# indoor_nearhandle_module.net
KiCad netlist of a schematic drawn in EAGLE
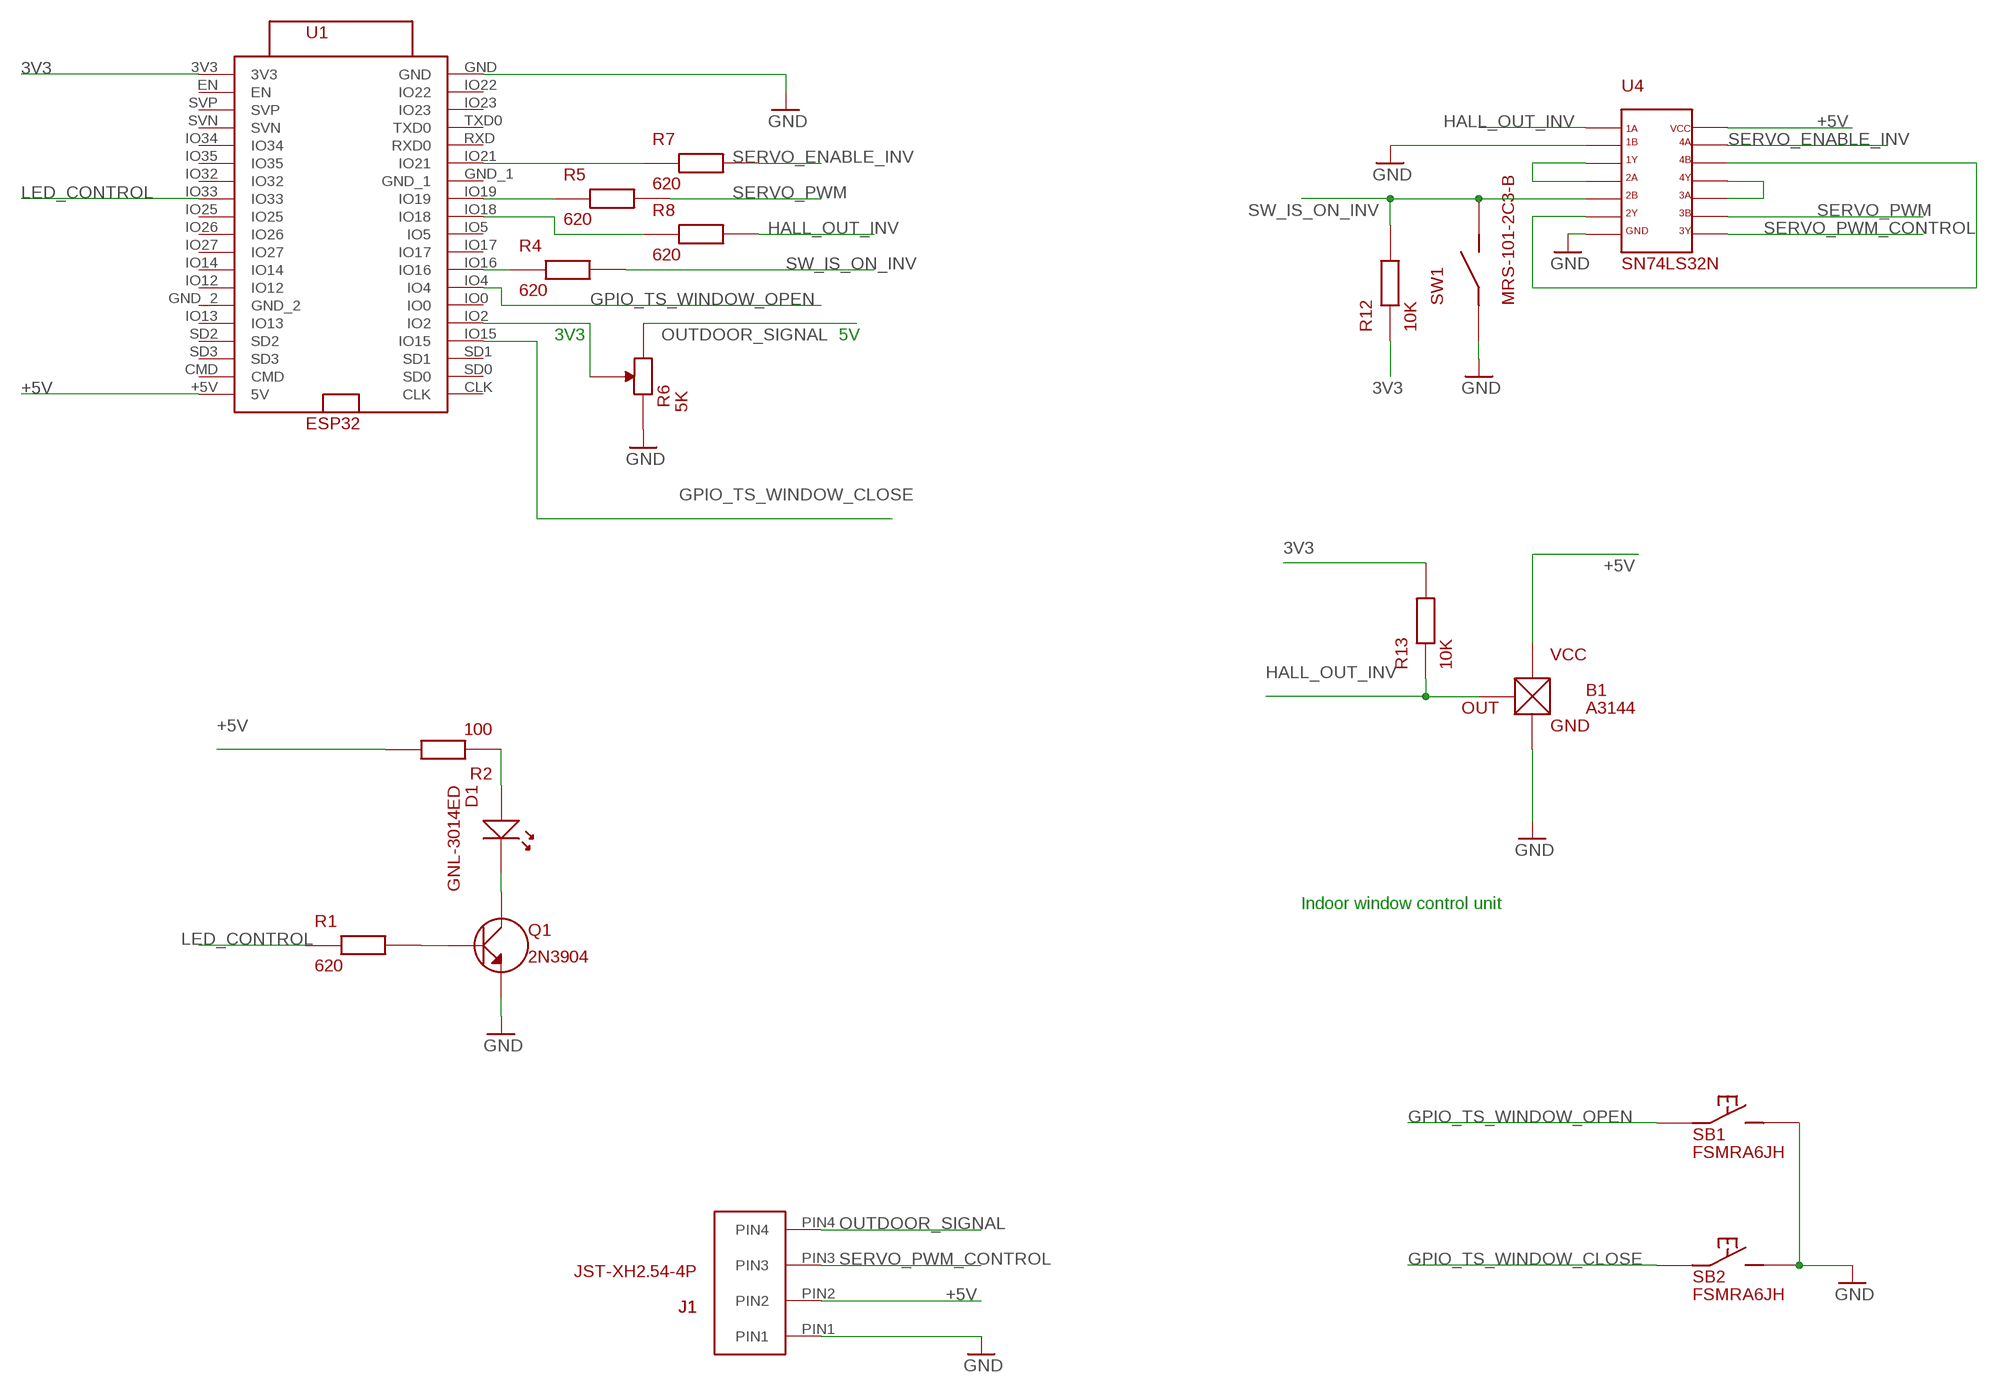
[diagram p0: schematic, sheet 1]

(export (version "E")
  (design (tool "Eeschema 10.0.6"))
  (components
    (comp (ref "B1")
      (value "A3144")
      (footprint "eagle-import:HALL_SENSOR")
      (libsource (lib "eagle-import") (part "HALL_SENSOR"))
    )
    (comp (ref "D1")
      (value "GNL-3014ED")
      (footprint "eagle-import:LD")
      (libsource (lib "eagle-import") (part "LD"))
    )
    (comp (ref "J1")
      (value "JST-XH2.54-4P")
      (footprint "eagle-import:JST-XH254-4P")
      (libsource (lib "eagle-import") (part "JST-XH254-4P"))
    )
    (comp (ref "Q1")
      (value "2N3904")
      (footprint "eagle-import:TRANSISTOR")
      (libsource (lib "eagle-import") (part "TRANSISTOR_NPN"))
    )
    (comp (ref "R1") (value "620") (footprint "eagle-import:R") (libsource (lib "eagle-import") (part "R")))
    (comp (ref "R2") (value "100") (footprint "eagle-import:R") (libsource (lib "eagle-import") (part "R")))
    (comp (ref "R4") (value "620") (footprint "eagle-import:R") (libsource (lib "eagle-import") (part "R")))
    (comp (ref "R5") (value "620") (footprint "eagle-import:R") (libsource (lib "eagle-import") (part "R")))
    (comp (ref "R6")
      (value "5K")
      (footprint "eagle-import:RD-3362H")
      (libsource (lib "eagle-import") (part "RD"))
    )
    (comp (ref "R7") (value "620") (footprint "eagle-import:R") (libsource (lib "eagle-import") (part "R")))
    (comp (ref "R8") (value "620") (footprint "eagle-import:R") (libsource (lib "eagle-import") (part "R")))
    (comp (ref "R12") (value "10K") (footprint "eagle-import:R") (libsource (lib "eagle-import") (part "R")))
    (comp (ref "R13") (value "10K") (footprint "eagle-import:R") (libsource (lib "eagle-import") (part "R")))
    (comp (ref "SB1")
      (value "FSMRA6JH")
      (footprint "eagle-import:SB-NO-SPST-ANGLE")
      (libsource (lib "eagle-import") (part "SB-NO"))
    )
    (comp (ref "SB2")
      (value "FSMRA6JH")
      (footprint "eagle-import:SB-NO-SPST-ANGLE")
      (libsource (lib "eagle-import") (part "SB-NO"))
    )
    (comp (ref "SW1")
      (value "MRS-101-2C3-B")
      (footprint "eagle-import:SWITCH")
      (libsource (lib "eagle-import") (part "SWITCH"))
    )
    (comp (ref "U1")
      (value "ESP32")
      (footprint "eagle-import:ESP32")
      (libsource (lib "eagle-import") (part "ESP32"))
    )
    (comp (ref "U4")
      (value "SN74LS32N")
      (footprint "eagle-import:DIP14")
      (libsource (lib "eagle-import") (part "SN74LS32N"))
    )
  )
  (nets
    (net (code "1") (name "/+5V") (class "Default")
      (node (ref "B1") (pin "VCC") (pinfunction "VCC_VCC") (pintype "power_in"))
      (node (ref "J1") (pin "PIN2") (pinfunction "PIN2_PIN2") (pintype "bidirectional"))
      (node (ref "R2") (pin "P$2") (pinfunction "P$2_P$2") (pintype "bidirectional"))
      (node (ref "U1") (pin "+5V") (pinfunction "5V_+5V") (pintype "power_in"))
      (node (ref "U4") (pin "PIN_14") (pinfunction "VCC_PIN_14") (pintype "power_in"))
    )
    (net (code "2") (name "/3V3") (class "Default")
      (node (ref "R12") (pin "P$1") (pinfunction "P$1_P$1") (pintype "bidirectional"))
      (node (ref "R13") (pin "P$2") (pinfunction "P$2_P$2") (pintype "bidirectional"))
      (node (ref "U1") (pin "3V3") (pinfunction "3V3_3V3") (pintype "power_in"))
    )
    (net (code "3") (name "/GPIO_TS_WINDOW_CLOSE") (class "Default")
      (node (ref "SB2") (pin "A") (pinfunction "P$1_A") (pintype "bidirectional"))
      (node (ref "U1") (pin "IO15") (pinfunction "IO15_IO15") (pintype "bidirectional"))
    )
    (net (code "4") (name "/GPIO_TS_WINDOW_OPEN") (class "Default")
      (node (ref "SB1") (pin "A") (pinfunction "P$1_A") (pintype "bidirectional"))
      (node (ref "U1") (pin "IO4") (pinfunction "IO4_IO4") (pintype "bidirectional"))
    )
    (net (code "5") (name "/HALL_OUT_INV") (class "Default")
      (node (ref "B1") (pin "OUT") (pinfunction "OUT_OUT") (pintype "bidirectional"))
      (node (ref "R13") (pin "P$1") (pinfunction "P$1_P$1") (pintype "bidirectional"))
      (node (ref "R8") (pin "P$2") (pinfunction "P$2_P$2") (pintype "bidirectional"))
      (node (ref "U4") (pin "PIN_1") (pinfunction "1A_PIN_1") (pintype "input"))
    )
    (net (code "6") (name "/LED_CONTROL") (class "Default")
      (node (ref "R1") (pin "P$1") (pinfunction "P$1_P$1") (pintype "bidirectional"))
      (node (ref "U1") (pin "IO33") (pinfunction "IO33_IO33") (pintype "bidirectional"))
    )
    (net (code "7") (name "/OUTDOOR_SIGNAL") (class "Default")
      (node (ref "J1") (pin "PIN4") (pinfunction "PIN4_PIN4") (pintype "bidirectional"))
      (node (ref "R6") (pin "P2") (pinfunction "P2_P2") (pintype "bidirectional"))
    )
    (net (code "8") (name "/SERVO_ENABLE_INV") (class "Default")
      (node (ref "R7") (pin "P$2") (pinfunction "P$2_P$2") (pintype "bidirectional"))
      (node (ref "U4") (pin "PIN_13") (pinfunction "4A_PIN_13") (pintype "input"))
    )
    (net (code "9") (name "/SERVO_PWM") (class "Default")
      (node (ref "R5") (pin "P$2") (pinfunction "P$2_P$2") (pintype "bidirectional"))
      (node (ref "U4") (pin "PIN_9") (pinfunction "3B_PIN_9") (pintype "input"))
    )
    (net (code "10") (name "/SERVO_PWM_CONTROL") (class "Default")
      (node (ref "J1") (pin "PIN3") (pinfunction "PIN3_PIN3") (pintype "bidirectional"))
      (node (ref "U4") (pin "PIN_8") (pinfunction "3Y_PIN_8") (pintype "output"))
    )
    (net (code "11") (name "/SW_IS_ON_INV") (class "Default")
      (node (ref "R12") (pin "P$2") (pinfunction "P$2_P$2") (pintype "bidirectional"))
      (node (ref "R4") (pin "P$2") (pinfunction "P$2_P$2") (pintype "bidirectional"))
      (node (ref "SW1") (pin "P$2") (pinfunction "P$2_P$2") (pintype "bidirectional"))
      (node (ref "U4") (pin "PIN_5") (pinfunction "2B_PIN_5") (pintype "input"))
    )
    (net (code "12") (name "GND") (class "Default")
      (node (ref "B1") (pin "GND") (pinfunction "GND_GND") (pintype "power_in"))
      (node (ref "J1") (pin "PIN1") (pinfunction "PIN1_PIN1") (pintype "bidirectional"))
      (node (ref "Q1") (pin "E") (pinfunction "E_E") (pintype "bidirectional"))
      (node (ref "R6") (pin "P1") (pinfunction "P1_P1") (pintype "bidirectional"))
      (node (ref "SB1") (pin "B") (pinfunction "P$2_B") (pintype "bidirectional"))
      (node (ref "SB2") (pin "B") (pinfunction "P$2_B") (pintype "bidirectional"))
      (node (ref "SW1") (pin "P$1") (pinfunction "P$1_P$1") (pintype "bidirectional"))
      (node (ref "U1") (pin "GND") (pinfunction "GND_GND") (pintype "power_in"))
      (node (ref "U4") (pin "PIN_2") (pinfunction "1B_PIN_2") (pintype "input"))
      (node (ref "U4") (pin "PIN_7") (pinfunction "GND_PIN_7") (pintype "power_in"))
    )
    (net (code "13") (name "Net-(D1-PadPIN_ANODE)") (class "Default")
      (node (ref "D1") (pin "PIN_ANODE") (pinfunction "PIN_ANODE_PIN_ANODE") (pintype "bidirectional"))
      (node (ref "Q1") (pin "C") (pinfunction "C_C") (pintype "bidirectional"))
    )
    (net (code "14") (name "Net-(D1-PadPIN_CATHODE)") (class "Default")
      (node (ref "D1") (pin "PIN_CATHODE") (pinfunction "PIN_CATHODE_PIN_CATHODE") (pintype "bidirectional"))
      (node (ref "R2") (pin "P$1") (pinfunction "P$1_P$1") (pintype "bidirectional"))
    )
    (net (code "15") (name "Net-(Q1-PadB)") (class "Default")
      (node (ref "Q1") (pin "B") (pinfunction "B_B") (pintype "bidirectional"))
      (node (ref "R1") (pin "P$2") (pinfunction "P$2_P$2") (pintype "bidirectional"))
    )
    (net (code "16") (name "Net-(R4-PadP$1)") (class "Default")
      (node (ref "R4") (pin "P$1") (pinfunction "P$1_P$1") (pintype "bidirectional"))
      (node (ref "U1") (pin "IO16") (pinfunction "IO16_IO16") (pintype "bidirectional"))
    )
    (net (code "17") (name "Net-(R5-PadP$1)") (class "Default")
      (node (ref "R5") (pin "P$1") (pinfunction "P$1_P$1") (pintype "bidirectional"))
      (node (ref "U1") (pin "IO19") (pinfunction "IO19_IO19") (pintype "bidirectional"))
    )
    (net (code "18") (name "Net-(R6-PadP3)") (class "Default")
      (node (ref "R6") (pin "P3") (pinfunction "P3_P3") (pintype "bidirectional"))
      (node (ref "U1") (pin "IO2") (pinfunction "IO2_IO2") (pintype "bidirectional"))
    )
    (net (code "19") (name "Net-(R7-PadP$1)") (class "Default")
      (node (ref "R7") (pin "P$1") (pinfunction "P$1_P$1") (pintype "bidirectional"))
      (node (ref "U1") (pin "IO21") (pinfunction "IO21_IO21") (pintype "bidirectional"))
    )
    (net (code "20") (name "Net-(R8-PadP$1)") (class "Default")
      (node (ref "R8") (pin "P$1") (pinfunction "P$1_P$1") (pintype "bidirectional"))
      (node (ref "U1") (pin "IO18") (pinfunction "IO18_IO18") (pintype "bidirectional"))
    )
    (net (code "21") (name "Net-(U4-1Y)") (class "Default")
      (node (ref "U4") (pin "PIN_3") (pinfunction "1Y_PIN_3") (pintype "output"))
      (node (ref "U4") (pin "PIN_4") (pinfunction "2A_PIN_4") (pintype "input"))
    )
    (net (code "22") (name "Net-(U4-2Y)") (class "Default")
      (node (ref "U4") (pin "PIN_12") (pinfunction "4B_PIN_12") (pintype "input"))
      (node (ref "U4") (pin "PIN_6") (pinfunction "2Y_PIN_6") (pintype "output"))
    )
    (net (code "23") (name "Net-(U4-3A)") (class "Default")
      (node (ref "U4") (pin "PIN_10") (pinfunction "3A_PIN_10") (pintype "input"))
      (node (ref "U4") (pin "PIN_11") (pinfunction "4Y_PIN_11") (pintype "output"))
    )
    (net (code "24") (name "unconnected-(U1-PadCLK)") (class "Default")
      (node (ref "U1") (pin "CLK") (pinfunction "CLK_CLK") (pintype "bidirectional"))
    )
    (net (code "25") (name "unconnected-(U1-PadCMD)") (class "Default")
      (node (ref "U1") (pin "CMD") (pinfunction "CMD_CMD") (pintype "bidirectional"))
    )
    (net (code "26") (name "unconnected-(U1-PadEN)") (class "Default")
      (node (ref "U1") (pin "EN") (pinfunction "EN_EN") (pintype "bidirectional"))
    )
    (net (code "27") (name "unconnected-(U1-PadGND_1)") (class "Default")
      (node (ref "U1") (pin "GND_1") (pinfunction "GND_1_GND_1") (pintype "bidirectional"))
    )
    (net (code "28") (name "unconnected-(U1-PadGND_2)") (class "Default")
      (node (ref "U1") (pin "GND_2") (pinfunction "GND_2_GND_2") (pintype "bidirectional"))
    )
    (net (code "29") (name "unconnected-(U1-PadIO0)") (class "Default")
      (node (ref "U1") (pin "IO0") (pinfunction "IO0_IO0") (pintype "bidirectional"))
    )
    (net (code "30") (name "unconnected-(U1-PadIO5)") (class "Default")
      (node (ref "U1") (pin "IO5") (pinfunction "IO5_IO5") (pintype "bidirectional"))
    )
    (net (code "31") (name "unconnected-(U1-PadIO12)") (class "Default")
      (node (ref "U1") (pin "IO12") (pinfunction "IO12_IO12") (pintype "bidirectional"))
    )
    (net (code "32") (name "unconnected-(U1-PadIO13)") (class "Default")
      (node (ref "U1") (pin "IO13") (pinfunction "IO13_IO13") (pintype "bidirectional"))
    )
    (net (code "33") (name "unconnected-(U1-PadIO14)") (class "Default")
      (node (ref "U1") (pin "IO14") (pinfunction "IO14_IO14") (pintype "bidirectional"))
    )
    (net (code "34") (name "unconnected-(U1-PadIO17)") (class "Default")
      (node (ref "U1") (pin "IO17") (pinfunction "IO17_IO17") (pintype "bidirectional"))
    )
    (net (code "35") (name "unconnected-(U1-PadIO22)") (class "Default")
      (node (ref "U1") (pin "IO22") (pinfunction "IO22_IO22") (pintype "bidirectional"))
    )
    (net (code "36") (name "unconnected-(U1-PadIO23)") (class "Default")
      (node (ref "U1") (pin "IO23") (pinfunction "IO23_IO23") (pintype "bidirectional"))
    )
    (net (code "37") (name "unconnected-(U1-PadIO25)") (class "Default")
      (node (ref "U1") (pin "IO25") (pinfunction "IO25_IO25") (pintype "bidirectional"))
    )
    (net (code "38") (name "unconnected-(U1-PadIO26)") (class "Default")
      (node (ref "U1") (pin "IO26") (pinfunction "IO26_IO26") (pintype "bidirectional"))
    )
    (net (code "39") (name "unconnected-(U1-PadIO27)") (class "Default")
      (node (ref "U1") (pin "IO27") (pinfunction "IO27_IO27") (pintype "bidirectional"))
    )
    (net (code "40") (name "unconnected-(U1-PadIO32)") (class "Default")
      (node (ref "U1") (pin "IO32") (pinfunction "IO32_IO32") (pintype "bidirectional"))
    )
    (net (code "41") (name "unconnected-(U1-PadIO34)") (class "Default")
      (node (ref "U1") (pin "IO34") (pinfunction "IO34_IO34") (pintype "bidirectional"))
    )
    (net (code "42") (name "unconnected-(U1-PadIO35)") (class "Default")
      (node (ref "U1") (pin "IO35") (pinfunction "IO35_IO35") (pintype "bidirectional"))
    )
    (net (code "43") (name "unconnected-(U1-PadSD0)") (class "Default")
      (node (ref "U1") (pin "SD0") (pinfunction "SD0_SD0") (pintype "bidirectional"))
    )
    (net (code "44") (name "unconnected-(U1-PadSD1)") (class "Default")
      (node (ref "U1") (pin "SD1") (pinfunction "SD1_SD1") (pintype "bidirectional"))
    )
    (net (code "45") (name "unconnected-(U1-PadSD2)") (class "Default")
      (node (ref "U1") (pin "SD2") (pinfunction "SD2_SD2") (pintype "bidirectional"))
    )
    (net (code "46") (name "unconnected-(U1-PadSD3)") (class "Default")
      (node (ref "U1") (pin "SD3") (pinfunction "SD3_SD3") (pintype "bidirectional"))
    )
    (net (code "47") (name "unconnected-(U1-PadSVN)") (class "Default")
      (node (ref "U1") (pin "SVN") (pinfunction "SVN_SVN") (pintype "bidirectional"))
    )
    (net (code "48") (name "unconnected-(U1-PadSVP)") (class "Default")
      (node (ref "U1") (pin "SVP") (pinfunction "SVP_SVP") (pintype "bidirectional"))
    )
    (net (code "49") (name "unconnected-(U1-PadTXD0)") (class "Default")
      (node (ref "U1") (pin "TXD0") (pinfunction "TXD0_TXD0") (pintype "bidirectional"))
    )
    (net (code "50") (name "unconnected-(U1-RXD0-PadRXD)") (class "Default")
      (node (ref "U1") (pin "RXD") (pinfunction "RXD0_RXD") (pintype "bidirectional"))
    )
  )
)
